# io_connectors.net
KiCad netlist of a schematic drawn in Altium Designer
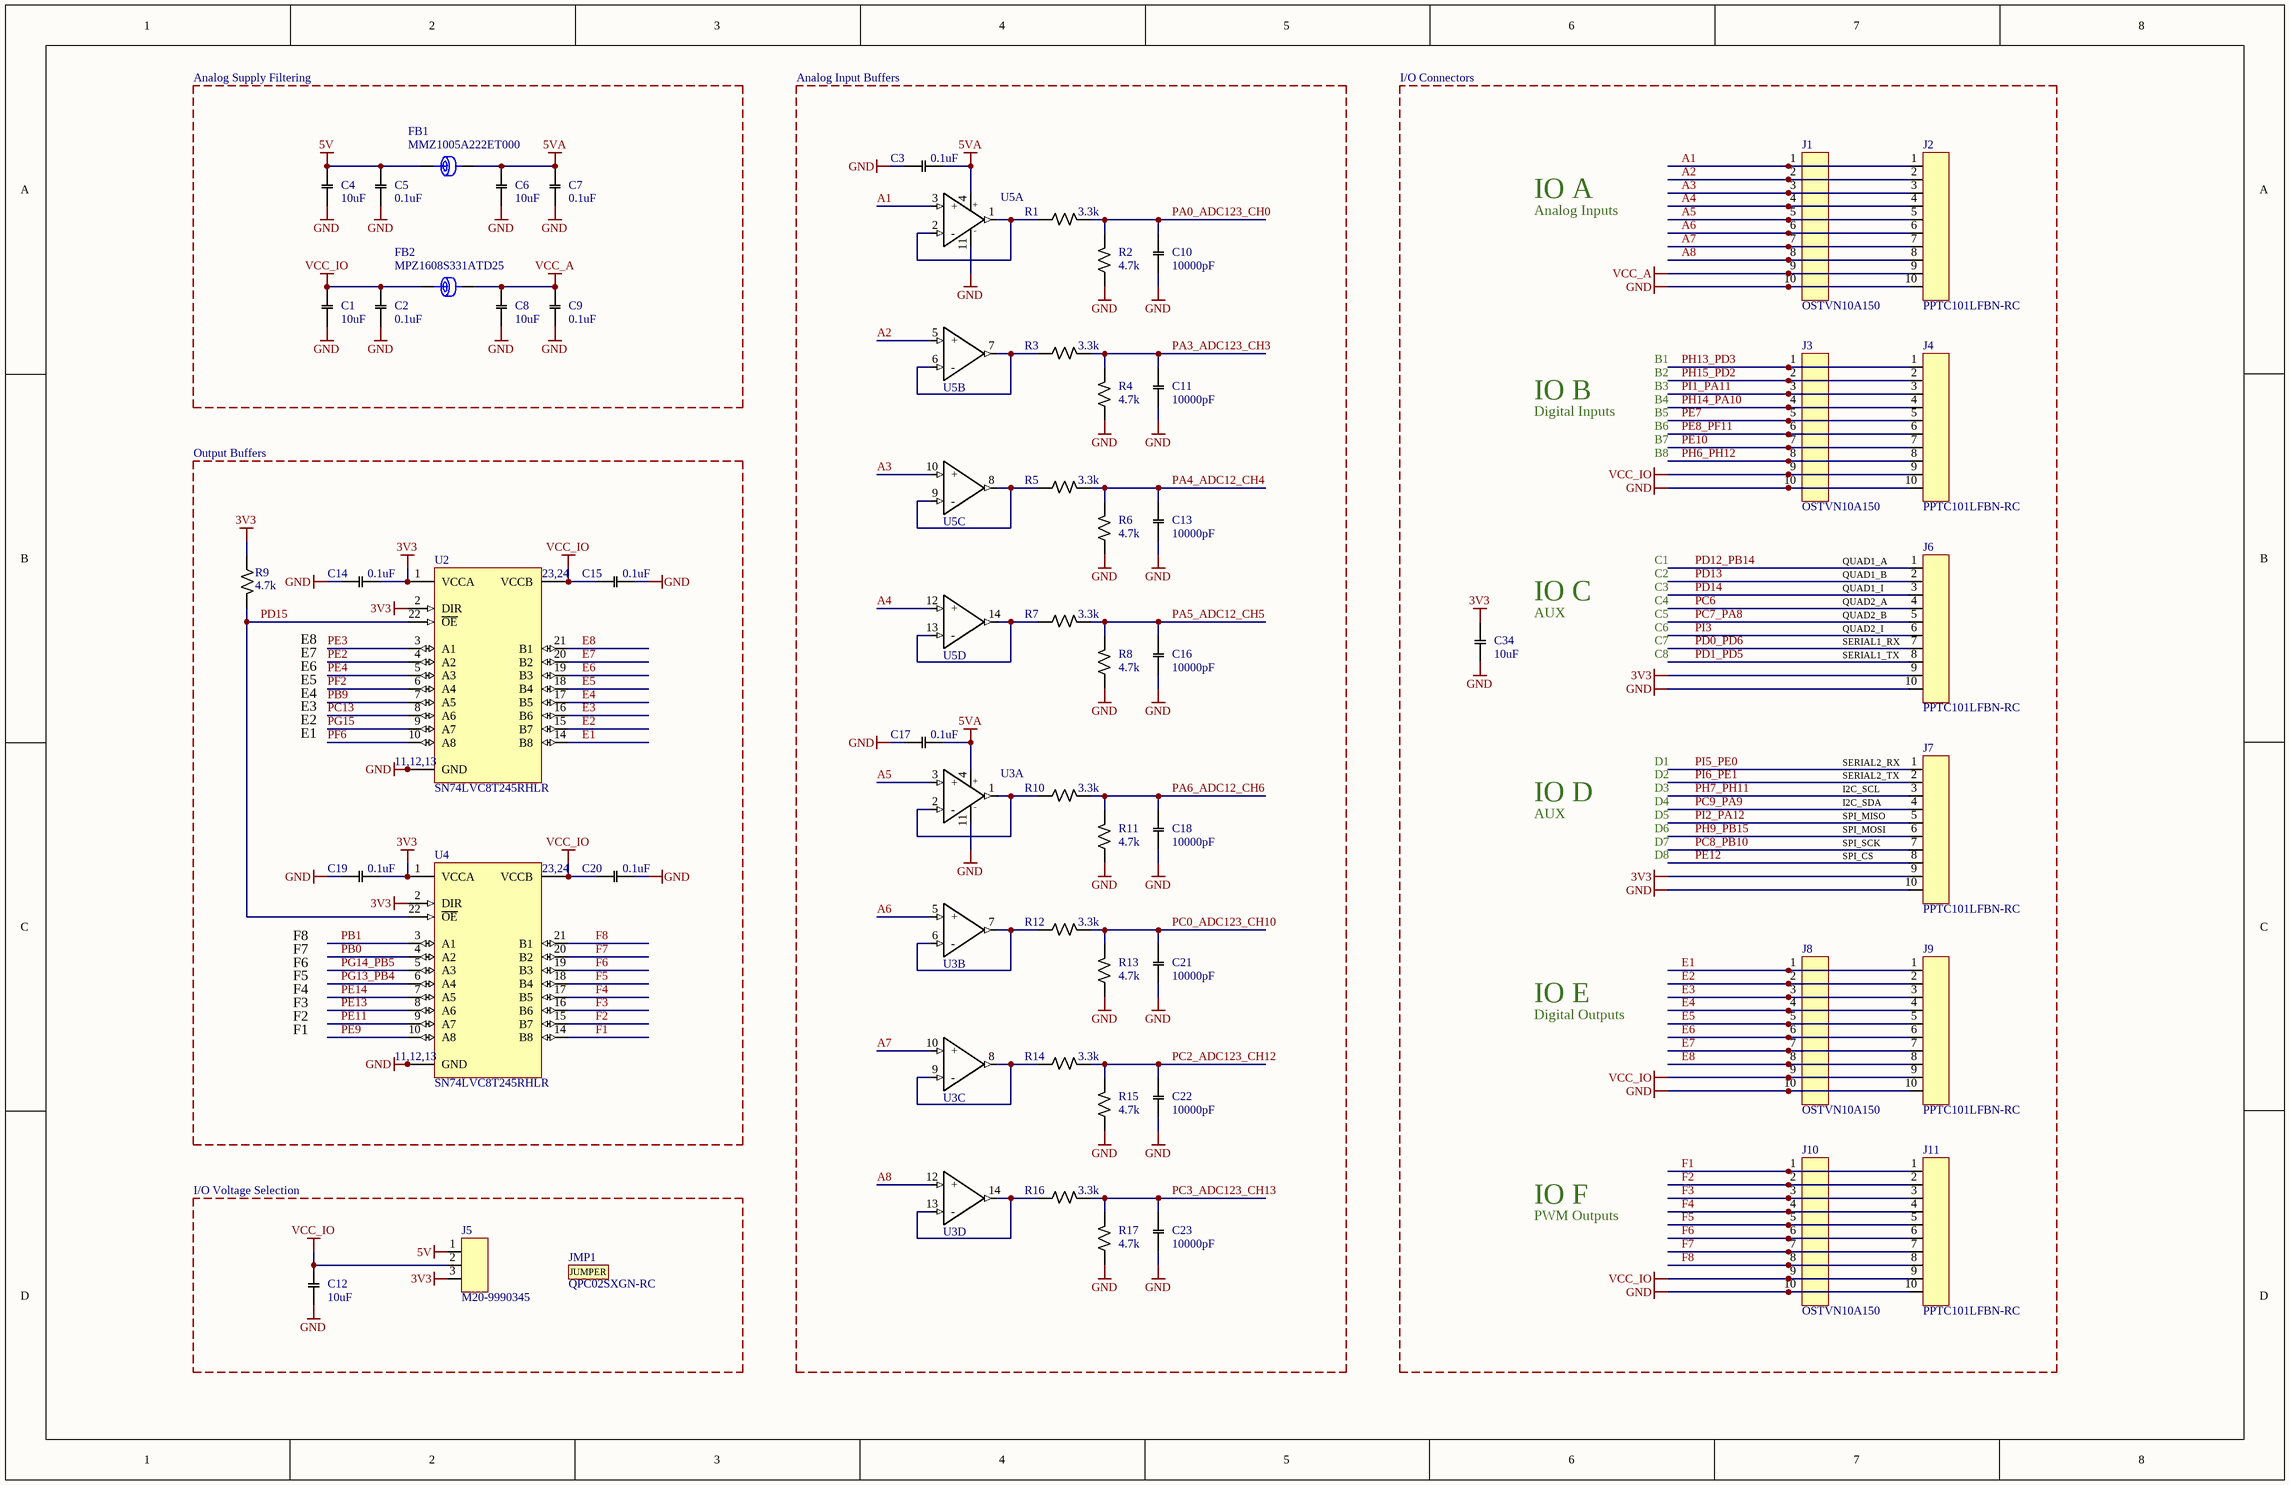
[diagram p0: io_connectors.SchDoc]

(export (version "E")
  (design (tool "Eeschema 10.0.6"))
  (components
    (comp (ref "C1")
      (value "C-10uf-X5R-25V-10%-0805")
      (footprint "C0805")
      (description "Capacitor Ceramic 10uF 25V X5R 10% SMD 0805")
      (fields (field (name "TOLERANCE") "10%") (field (name "CAPACITANCE") "10uF"))
      (libsource (lib "Hebi Robotics") (part "Capacitor"))
    )
    (comp (ref "C2")
      (value "C-0.1uf-X7R-25V-10%-0402")
      (footprint "C0402")
      (description "Capacitor Ceramic 0.1uF 25V X7R 10% SMD 0402")
      (fields (field (name "TOLERANCE") "10%") (field (name "CAPACITANCE") "0.1uF"))
      (libsource (lib "Hebi Robotics") (part "Capacitor"))
    )
    (comp (ref "C3")
      (value "C-0.1uf-X7R-25V-10%-0402")
      (footprint "C0402")
      (description "Capacitor Ceramic 0.1uF 25V X7R 10% SMD 0402")
      (fields (field (name "TOLERANCE") "10%") (field (name "CAPACITANCE") "0.1uF"))
      (libsource (lib "Hebi Robotics") (part "Capacitor"))
    )
    (comp (ref "C4")
      (value "C-10uf-X5R-25V-10%-0805")
      (footprint "C0805")
      (description "Capacitor Ceramic 10uF 25V X5R 10% SMD 0805")
      (fields (field (name "TOLERANCE") "10%") (field (name "CAPACITANCE") "10uF"))
      (libsource (lib "Hebi Robotics") (part "Capacitor"))
    )
    (comp (ref "C5")
      (value "C-0.1uf-X7R-25V-10%-0402")
      (footprint "C0402")
      (description "Capacitor Ceramic 0.1uF 25V X7R 10% SMD 0402")
      (fields (field (name "TOLERANCE") "10%") (field (name "CAPACITANCE") "0.1uF"))
      (libsource (lib "Hebi Robotics") (part "Capacitor"))
    )
    (comp (ref "C6")
      (value "C-10uf-X5R-25V-10%-0805")
      (footprint "C0805")
      (description "Capacitor Ceramic 10uF 25V X5R 10% SMD 0805")
      (fields (field (name "TOLERANCE") "10%") (field (name "CAPACITANCE") "10uF"))
      (libsource (lib "Hebi Robotics") (part "Capacitor"))
    )
    (comp (ref "C7")
      (value "C-0.1uf-X7R-25V-10%-0402")
      (footprint "C0402")
      (description "Capacitor Ceramic 0.1uF 25V X7R 10% SMD 0402")
      (fields (field (name "TOLERANCE") "10%") (field (name "CAPACITANCE") "0.1uF"))
      (libsource (lib "Hebi Robotics") (part "Capacitor"))
    )
    (comp (ref "C8")
      (value "C-10uf-X5R-25V-10%-0805")
      (footprint "C0805")
      (description "Capacitor Ceramic 10uF 25V X5R 10% SMD 0805")
      (fields (field (name "TOLERANCE") "10%") (field (name "CAPACITANCE") "10uF"))
      (libsource (lib "Hebi Robotics") (part "Capacitor"))
    )
    (comp (ref "C9")
      (value "C-0.1uf-X7R-25V-10%-0402")
      (footprint "C0402")
      (description "Capacitor Ceramic 0.1uF 25V X7R 10% SMD 0402")
      (fields (field (name "TOLERANCE") "10%") (field (name "CAPACITANCE") "0.1uF"))
      (libsource (lib "Hebi Robotics") (part "Capacitor"))
    )
    (comp (ref "C10")
      (value "C-10000pf-X7R-50V-10%-0402")
      (footprint "C0402")
      (description "Capacitor Ceramic 10000pF 50V X7R 10% SMD 0402")
      (fields (field (name "TOLERANCE") "10%") (field (name "CAPACITANCE") "10000pF"))
      (libsource (lib "Hebi Robotics") (part "Capacitor"))
    )
    (comp (ref "C11")
      (value "C-10000pf-X7R-50V-10%-0402")
      (footprint "C0402")
      (description "Capacitor Ceramic 10000pF 50V X7R 10% SMD 0402")
      (fields (field (name "TOLERANCE") "10%") (field (name "CAPACITANCE") "10000pF"))
      (libsource (lib "Hebi Robotics") (part "Capacitor"))
    )
    (comp (ref "C12")
      (value "C-10uf-X5R-25V-10%-0805")
      (footprint "C0805")
      (description "Capacitor Ceramic 10uF 25V X5R 10% SMD 0805")
      (fields (field (name "TOLERANCE") "10%") (field (name "CAPACITANCE") "10uF"))
      (libsource (lib "Hebi Robotics") (part "Capacitor"))
    )
    (comp (ref "C13")
      (value "C-10000pf-X7R-50V-10%-0402")
      (footprint "C0402")
      (description "Capacitor Ceramic 10000pF 50V X7R 10% SMD 0402")
      (fields (field (name "TOLERANCE") "10%") (field (name "CAPACITANCE") "10000pF"))
      (libsource (lib "Hebi Robotics") (part "Capacitor"))
    )
    (comp (ref "C14")
      (value "C-0.1uf-X7R-25V-10%-0402")
      (footprint "C0402")
      (description "Capacitor Ceramic 0.1uF 25V X7R 10% SMD 0402")
      (fields (field (name "TOLERANCE") "10%") (field (name "CAPACITANCE") "0.1uF"))
      (libsource (lib "Hebi Robotics") (part "Capacitor"))
    )
    (comp (ref "C15")
      (value "C-0.1uf-X7R-25V-10%-0402")
      (footprint "C0402")
      (description "Capacitor Ceramic 0.1uF 25V X7R 10% SMD 0402")
      (fields (field (name "TOLERANCE") "10%") (field (name "CAPACITANCE") "0.1uF"))
      (libsource (lib "Hebi Robotics") (part "Capacitor"))
    )
    (comp (ref "C16")
      (value "C-10000pf-X7R-50V-10%-0402")
      (footprint "C0402")
      (description "Capacitor Ceramic 10000pF 50V X7R 10% SMD 0402")
      (fields (field (name "TOLERANCE") "10%") (field (name "CAPACITANCE") "10000pF"))
      (libsource (lib "Hebi Robotics") (part "Capacitor"))
    )
    (comp (ref "C17")
      (value "C-0.1uf-X7R-25V-10%-0402")
      (footprint "C0402")
      (description "Capacitor Ceramic 0.1uF 25V X7R 10% SMD 0402")
      (fields (field (name "TOLERANCE") "10%") (field (name "CAPACITANCE") "0.1uF"))
      (libsource (lib "Hebi Robotics") (part "Capacitor"))
    )
    (comp (ref "C18")
      (value "C-10000pf-X7R-50V-10%-0402")
      (footprint "C0402")
      (description "Capacitor Ceramic 10000pF 50V X7R 10% SMD 0402")
      (fields (field (name "TOLERANCE") "10%") (field (name "CAPACITANCE") "10000pF"))
      (libsource (lib "Hebi Robotics") (part "Capacitor"))
    )
    (comp (ref "C19")
      (value "C-0.1uf-X7R-25V-10%-0402")
      (footprint "C0402")
      (description "Capacitor Ceramic 0.1uF 25V X7R 10% SMD 0402")
      (fields (field (name "TOLERANCE") "10%") (field (name "CAPACITANCE") "0.1uF"))
      (libsource (lib "Hebi Robotics") (part "Capacitor"))
    )
    (comp (ref "C20")
      (value "C-0.1uf-X7R-25V-10%-0402")
      (footprint "C0402")
      (description "Capacitor Ceramic 0.1uF 25V X7R 10% SMD 0402")
      (fields (field (name "TOLERANCE") "10%") (field (name "CAPACITANCE") "0.1uF"))
      (libsource (lib "Hebi Robotics") (part "Capacitor"))
    )
    (comp (ref "C21")
      (value "C-10000pf-X7R-50V-10%-0402")
      (footprint "C0402")
      (description "Capacitor Ceramic 10000pF 50V X7R 10% SMD 0402")
      (fields (field (name "TOLERANCE") "10%") (field (name "CAPACITANCE") "10000pF"))
      (libsource (lib "Hebi Robotics") (part "Capacitor"))
    )
    (comp (ref "C22")
      (value "C-10000pf-X7R-50V-10%-0402")
      (footprint "C0402")
      (description "Capacitor Ceramic 10000pF 50V X7R 10% SMD 0402")
      (fields (field (name "TOLERANCE") "10%") (field (name "CAPACITANCE") "10000pF"))
      (libsource (lib "Hebi Robotics") (part "Capacitor"))
    )
    (comp (ref "C23")
      (value "C-10000pf-X7R-50V-10%-0402")
      (footprint "C0402")
      (description "Capacitor Ceramic 10000pF 50V X7R 10% SMD 0402")
      (fields (field (name "TOLERANCE") "10%") (field (name "CAPACITANCE") "10000pF"))
      (libsource (lib "Hebi Robotics") (part "Capacitor"))
    )
    (comp (ref "C34")
      (value "C-10uf-X5R-25V-10%-0805")
      (footprint "C0805")
      (description "Capacitor Ceramic 10uF 25V X5R 10% SMD 0805")
      (fields (field (name "TOLERANCE") "10%") (field (name "CAPACITANCE") "10uF"))
      (libsource (lib "Hebi Robotics") (part "Capacitor"))
    )
    (comp (ref "FB1")
      (value "MMZ1005A222ET000")
      (footprint "FB0402")
      (description "FERRITE BEAD 2.2 KOHM 0402 1LN")
      (libsource (lib "Hebi Robotics") (part "FB"))
    )
    (comp (ref "FB2")
      (value "MPZ1608S331ATD25")
      (footprint "FB0603")
      (description "FERRITE CHIP 330 OHM 1.7A 0603")
      (libsource (lib "Hebi Robotics") (part "FB"))
    )
    (comp (ref "J1")
      (value "OSTVN10A150")
      (footprint "OSTVN10A150")
      (description "CONN TERM BLOCK 2.54MM 10POS PCB")
      (fields (field (name "MANUFACTURER") "On Shore Technology Inc.") (field (name "VOLTAGE") "125V"))
      (libsource (lib "Hebi Robotics") (part "CONN_1_ROW_010_POS"))
    )
    (comp (ref "J2")
      (value "PPTC101LFBN-RC")
      (footprint "PPTC101LFBN-RC")
      (description "CONN HEADER FEMALE 10POS.1\" TIN")
      (fields (field (name "MANUFACTURER") "Sullins Connector Solutions"))
      (libsource (lib "Hebi Robotics") (part "CONN_1_ROW_010_POS"))
    )
    (comp (ref "J3")
      (value "OSTVN10A150")
      (footprint "OSTVN10A150")
      (description "CONN TERM BLOCK 2.54MM 10POS PCB")
      (fields (field (name "MANUFACTURER") "On Shore Technology Inc.") (field (name "VOLTAGE") "125V"))
      (libsource (lib "Hebi Robotics") (part "CONN_1_ROW_010_POS"))
    )
    (comp (ref "J4")
      (value "PPTC101LFBN-RC")
      (footprint "PPTC101LFBN-RC")
      (description "CONN HEADER FEMALE 10POS.1\" TIN")
      (fields (field (name "MANUFACTURER") "Sullins Connector Solutions"))
      (libsource (lib "Hebi Robotics") (part "CONN_1_ROW_010_POS"))
    )
    (comp (ref "J5")
      (value "M20-9990345")
      (footprint "M20-9990345")
      (description "CONN HEADER VERT 3POS 2.54MM")
      (fields (field (name "MANUFACTURER") "Harwin Inc."))
      (libsource (lib "Hebi Robotics") (part "CONN_1_ROW_003_POS"))
    )
    (comp (ref "J6")
      (value "PPTC101LFBN-RC")
      (footprint "PPTC101LFBN-RC")
      (description "CONN HEADER FEMALE 10POS.1\" TIN")
      (fields (field (name "MANUFACTURER") "Sullins Connector Solutions"))
      (libsource (lib "Hebi Robotics") (part "CONN_1_ROW_010_POS"))
    )
    (comp (ref "J7")
      (value "PPTC101LFBN-RC")
      (footprint "PPTC101LFBN-RC")
      (description "CONN HEADER FEMALE 10POS.1\" TIN")
      (fields (field (name "MANUFACTURER") "Sullins Connector Solutions"))
      (libsource (lib "Hebi Robotics") (part "CONN_1_ROW_010_POS"))
    )
    (comp (ref "J8")
      (value "OSTVN10A150")
      (footprint "OSTVN10A150")
      (description "CONN TERM BLOCK 2.54MM 10POS PCB")
      (fields (field (name "MANUFACTURER") "On Shore Technology Inc.") (field (name "VOLTAGE") "125V"))
      (libsource (lib "Hebi Robotics") (part "CONN_1_ROW_010_POS"))
    )
    (comp (ref "J9")
      (value "PPTC101LFBN-RC")
      (footprint "PPTC101LFBN-RC")
      (description "CONN HEADER FEMALE 10POS.1\" TIN")
      (fields (field (name "MANUFACTURER") "Sullins Connector Solutions"))
      (libsource (lib "Hebi Robotics") (part "CONN_1_ROW_010_POS"))
    )
    (comp (ref "J10")
      (value "OSTVN10A150")
      (footprint "OSTVN10A150")
      (description "CONN TERM BLOCK 2.54MM 10POS PCB")
      (fields (field (name "MANUFACTURER") "On Shore Technology Inc.") (field (name "VOLTAGE") "125V"))
      (libsource (lib "Hebi Robotics") (part "CONN_1_ROW_010_POS"))
    )
    (comp (ref "J11")
      (value "PPTC101LFBN-RC")
      (footprint "PPTC101LFBN-RC")
      (description "CONN HEADER FEMALE 10POS.1\" TIN")
      (fields (field (name "MANUFACTURER") "Sullins Connector Solutions"))
      (libsource (lib "Hebi Robotics") (part "CONN_1_ROW_010_POS"))
    )
    (comp (ref "JMP1")
      (value "QPC02SXGN-RC")
      (description "CONN JUMPER SHORTING .100\" GOLD")
      (fields (field (name "MANUFACTURER") "Sullins"))
      (libsource (lib "Hebi Robotics") (part "JUMPER_2"))
    )
    (comp (ref "R1")
      (value "R-3.3k-0.1%-0.063w-0402")
      (footprint "R0402")
      (description "Resistor 0402 3.3k Ohm 0.1% 1-16 Watt")
      (fields (field (name "POWER") "0.063W, 1/16W") (field (name "RESISTANCE") "3.3k"))
      (libsource (lib "Hebi Robotics") (part "Resistor"))
    )
    (comp (ref "R2")
      (value "R-4.7k-0.1%-0.063w-0402")
      (footprint "R0402")
      (description "Resistor 0402 4.7k Ohm 0.1% 1-16 Watt")
      (fields (field (name "POWER") "0.063W, 1/16W") (field (name "RESISTANCE") "4.7k"))
      (libsource (lib "Hebi Robotics") (part "Resistor"))
    )
    (comp (ref "R3")
      (value "R-3.3k-0.1%-0.063w-0402")
      (footprint "R0402")
      (description "Resistor 0402 3.3k Ohm 0.1% 1-16 Watt")
      (fields (field (name "POWER") "0.063W, 1/16W") (field (name "RESISTANCE") "3.3k"))
      (libsource (lib "Hebi Robotics") (part "Resistor"))
    )
    (comp (ref "R4")
      (value "R-4.7k-0.1%-0.063w-0402")
      (footprint "R0402")
      (description "Resistor 0402 4.7k Ohm 0.1% 1-16 Watt")
      (fields (field (name "POWER") "0.063W, 1/16W") (field (name "RESISTANCE") "4.7k"))
      (libsource (lib "Hebi Robotics") (part "Resistor"))
    )
    (comp (ref "R5")
      (value "R-3.3k-0.1%-0.063w-0402")
      (footprint "R0402")
      (description "Resistor 0402 3.3k Ohm 0.1% 1-16 Watt")
      (fields (field (name "POWER") "0.063W, 1/16W") (field (name "RESISTANCE") "3.3k"))
      (libsource (lib "Hebi Robotics") (part "Resistor"))
    )
    (comp (ref "R6")
      (value "R-4.7k-0.1%-0.063w-0402")
      (footprint "R0402")
      (description "Resistor 0402 4.7k Ohm 0.1% 1-16 Watt")
      (fields (field (name "POWER") "0.063W, 1/16W") (field (name "RESISTANCE") "4.7k"))
      (libsource (lib "Hebi Robotics") (part "Resistor"))
    )
    (comp (ref "R7")
      (value "R-3.3k-0.1%-0.063w-0402")
      (footprint "R0402")
      (description "Resistor 0402 3.3k Ohm 0.1% 1-16 Watt")
      (fields (field (name "POWER") "0.063W, 1/16W") (field (name "RESISTANCE") "3.3k"))
      (libsource (lib "Hebi Robotics") (part "Resistor"))
    )
    (comp (ref "R8")
      (value "R-4.7k-0.1%-0.063w-0402")
      (footprint "R0402")
      (description "Resistor 0402 4.7k Ohm 0.1% 1-16 Watt")
      (fields (field (name "POWER") "0.063W, 1/16W") (field (name "RESISTANCE") "4.7k"))
      (libsource (lib "Hebi Robotics") (part "Resistor"))
    )
    (comp (ref "R9")
      (value "R-4.7k-1%-0.063w-0402")
      (footprint "R0402")
      (description "Resistor 0402 4.7k Ohm 1% 1-16 Watt")
      (fields (field (name "POWER") "0.063W, 1/16W") (field (name "RESISTANCE") "4.7k"))
      (libsource (lib "Hebi Robotics") (part "Resistor"))
    )
    (comp (ref "R10")
      (value "R-3.3k-0.1%-0.063w-0402")
      (footprint "R0402")
      (description "Resistor 0402 3.3k Ohm 0.1% 1-16 Watt")
      (fields (field (name "POWER") "0.063W, 1/16W") (field (name "RESISTANCE") "3.3k"))
      (libsource (lib "Hebi Robotics") (part "Resistor"))
    )
    (comp (ref "R11")
      (value "R-4.7k-0.1%-0.063w-0402")
      (footprint "R0402")
      (description "Resistor 0402 4.7k Ohm 0.1% 1-16 Watt")
      (fields (field (name "POWER") "0.063W, 1/16W") (field (name "RESISTANCE") "4.7k"))
      (libsource (lib "Hebi Robotics") (part "Resistor"))
    )
    (comp (ref "R12")
      (value "R-3.3k-0.1%-0.063w-0402")
      (footprint "R0402")
      (description "Resistor 0402 3.3k Ohm 0.1% 1-16 Watt")
      (fields (field (name "POWER") "0.063W, 1/16W") (field (name "RESISTANCE") "3.3k"))
      (libsource (lib "Hebi Robotics") (part "Resistor"))
    )
    (comp (ref "R13")
      (value "R-4.7k-0.1%-0.063w-0402")
      (footprint "R0402")
      (description "Resistor 0402 4.7k Ohm 0.1% 1-16 Watt")
      (fields (field (name "POWER") "0.063W, 1/16W") (field (name "RESISTANCE") "4.7k"))
      (libsource (lib "Hebi Robotics") (part "Resistor"))
    )
    (comp (ref "R14")
      (value "R-3.3k-0.1%-0.063w-0402")
      (footprint "R0402")
      (description "Resistor 0402 3.3k Ohm 0.1% 1-16 Watt")
      (fields (field (name "POWER") "0.063W, 1/16W") (field (name "RESISTANCE") "3.3k"))
      (libsource (lib "Hebi Robotics") (part "Resistor"))
    )
    (comp (ref "R15")
      (value "R-4.7k-0.1%-0.063w-0402")
      (footprint "R0402")
      (description "Resistor 0402 4.7k Ohm 0.1% 1-16 Watt")
      (fields (field (name "POWER") "0.063W, 1/16W") (field (name "RESISTANCE") "4.7k"))
      (libsource (lib "Hebi Robotics") (part "Resistor"))
    )
    (comp (ref "R16")
      (value "R-3.3k-0.1%-0.063w-0402")
      (footprint "R0402")
      (description "Resistor 0402 3.3k Ohm 0.1% 1-16 Watt")
      (fields (field (name "POWER") "0.063W, 1/16W") (field (name "RESISTANCE") "3.3k"))
      (libsource (lib "Hebi Robotics") (part "Resistor"))
    )
    (comp (ref "R17")
      (value "R-4.7k-0.1%-0.063w-0402")
      (footprint "R0402")
      (description "Resistor 0402 4.7k Ohm 0.1% 1-16 Watt")
      (fields (field (name "POWER") "0.063W, 1/16W") (field (name "RESISTANCE") "4.7k"))
      (libsource (lib "Hebi Robotics") (part "Resistor"))
    )
    (comp (ref "U2")
      (value "SN74LVC8T245RHLR")
      (footprint "R-PVQFN-N24_TI")
      (description "IC BUS TRANSCVR 8BIT 24QFN")
      (libsource (lib "Hebi Robotics") (part "SN74LVC8T245"))
    )
    (comp (ref "U3")
      (value "TSV324IPT")
      (footprint "TSSOP14_ST")
      (description "IC OPAMP GP 1.4MHZ RRO 14TSSOP")
      (fields (field (name "MANUFACTURER") "STMicroelectronics"))
      (libsource (lib "Hebi Robotics") (part "Symbol"))
    )
    (comp (ref "U4")
      (value "SN74LVC8T245RHLR")
      (footprint "R-PVQFN-N24_TI")
      (description "IC BUS TRANSCVR 8BIT 24QFN")
      (libsource (lib "Hebi Robotics") (part "SN74LVC8T245"))
    )
    (comp (ref "U5")
      (value "TSV324IPT")
      (footprint "TSSOP14_ST")
      (description "IC OPAMP GP 1.4MHZ RRO 14TSSOP")
      (fields (field (name "MANUFACTURER") "STMicroelectronics"))
      (libsource (lib "Hebi Robotics") (part "Symbol"))
    )
  )
  (nets
    (net (code "1") (name "/A1") (class "Default")
      (node (ref "J1") (pin "1") (pinfunction "1_1") (pintype "passive"))
      (node (ref "J2") (pin "1") (pinfunction "1_1") (pintype "passive"))
      (node (ref "U5") (pin "3") (pinfunction "+_3") (pintype "input"))
    )
    (net (code "2") (name "/A2") (class "Default")
      (node (ref "J1") (pin "2") (pinfunction "2_2") (pintype "passive"))
      (node (ref "J2") (pin "2") (pinfunction "2_2") (pintype "passive"))
      (node (ref "U5") (pin "5") (pinfunction "+_5") (pintype "input"))
    )
    (net (code "3") (name "/A3") (class "Default")
      (node (ref "J1") (pin "3") (pinfunction "3_3") (pintype "passive"))
      (node (ref "J2") (pin "3") (pinfunction "3_3") (pintype "passive"))
      (node (ref "U5") (pin "10") (pinfunction "+_10") (pintype "input"))
    )
    (net (code "4") (name "/A4") (class "Default")
      (node (ref "J1") (pin "4") (pinfunction "4_4") (pintype "passive"))
      (node (ref "J2") (pin "4") (pinfunction "4_4") (pintype "passive"))
      (node (ref "U5") (pin "12") (pinfunction "+_12") (pintype "input"))
    )
    (net (code "5") (name "/A5") (class "Default")
      (node (ref "J1") (pin "5") (pinfunction "5_5") (pintype "passive"))
      (node (ref "J2") (pin "5") (pinfunction "5_5") (pintype "passive"))
      (node (ref "U3") (pin "3") (pinfunction "+_3") (pintype "input"))
    )
    (net (code "6") (name "/A6") (class "Default")
      (node (ref "J1") (pin "6") (pinfunction "6_6") (pintype "passive"))
      (node (ref "J2") (pin "6") (pinfunction "6_6") (pintype "passive"))
      (node (ref "U3") (pin "5") (pinfunction "+_5") (pintype "input"))
    )
    (net (code "7") (name "/A7") (class "Default")
      (node (ref "J1") (pin "7") (pinfunction "7_7") (pintype "passive"))
      (node (ref "J2") (pin "7") (pinfunction "7_7") (pintype "passive"))
      (node (ref "U3") (pin "10") (pinfunction "+_10") (pintype "input"))
    )
    (net (code "8") (name "/A8") (class "Default")
      (node (ref "J1") (pin "8") (pinfunction "8_8") (pintype "passive"))
      (node (ref "J2") (pin "8") (pinfunction "8_8") (pintype "passive"))
      (node (ref "U3") (pin "12") (pinfunction "+_12") (pintype "input"))
    )
    (net (code "9") (name "/E1") (class "Default")
      (node (ref "J8") (pin "1") (pinfunction "1_1") (pintype "passive"))
      (node (ref "J9") (pin "1") (pinfunction "1_1") (pintype "passive"))
      (node (ref "U2") (pin "14") (pinfunction "B8_14") (pintype "bidirectional"))
    )
    (net (code "10") (name "/E2") (class "Default")
      (node (ref "J8") (pin "2") (pinfunction "2_2") (pintype "passive"))
      (node (ref "J9") (pin "2") (pinfunction "2_2") (pintype "passive"))
      (node (ref "U2") (pin "15") (pinfunction "B7_15") (pintype "bidirectional"))
    )
    (net (code "11") (name "/E3") (class "Default")
      (node (ref "J8") (pin "3") (pinfunction "3_3") (pintype "passive"))
      (node (ref "J9") (pin "3") (pinfunction "3_3") (pintype "passive"))
      (node (ref "U2") (pin "16") (pinfunction "B6_16") (pintype "bidirectional"))
    )
    (net (code "12") (name "/E4") (class "Default")
      (node (ref "J8") (pin "4") (pinfunction "4_4") (pintype "passive"))
      (node (ref "J9") (pin "4") (pinfunction "4_4") (pintype "passive"))
      (node (ref "U2") (pin "17") (pinfunction "B5_17") (pintype "bidirectional"))
    )
    (net (code "13") (name "/E5") (class "Default")
      (node (ref "J8") (pin "5") (pinfunction "5_5") (pintype "passive"))
      (node (ref "J9") (pin "5") (pinfunction "5_5") (pintype "passive"))
      (node (ref "U2") (pin "18") (pinfunction "B4_18") (pintype "bidirectional"))
    )
    (net (code "14") (name "/E6") (class "Default")
      (node (ref "J8") (pin "6") (pinfunction "6_6") (pintype "passive"))
      (node (ref "J9") (pin "6") (pinfunction "6_6") (pintype "passive"))
      (node (ref "U2") (pin "19") (pinfunction "B3_19") (pintype "bidirectional"))
    )
    (net (code "15") (name "/E7") (class "Default")
      (node (ref "J8") (pin "7") (pinfunction "7_7") (pintype "passive"))
      (node (ref "J9") (pin "7") (pinfunction "7_7") (pintype "passive"))
      (node (ref "U2") (pin "20") (pinfunction "B2_20") (pintype "bidirectional"))
    )
    (net (code "16") (name "/E8") (class "Default")
      (node (ref "J8") (pin "8") (pinfunction "8_8") (pintype "passive"))
      (node (ref "J9") (pin "8") (pinfunction "8_8") (pintype "passive"))
      (node (ref "U2") (pin "21") (pinfunction "B1_21") (pintype "bidirectional"))
    )
    (net (code "17") (name "/F1") (class "Default")
      (node (ref "J10") (pin "1") (pinfunction "1_1") (pintype "passive"))
      (node (ref "J11") (pin "1") (pinfunction "1_1") (pintype "passive"))
      (node (ref "U4") (pin "14") (pinfunction "B8_14") (pintype "bidirectional"))
    )
    (net (code "18") (name "/F2") (class "Default")
      (node (ref "J10") (pin "2") (pinfunction "2_2") (pintype "passive"))
      (node (ref "J11") (pin "2") (pinfunction "2_2") (pintype "passive"))
      (node (ref "U4") (pin "15") (pinfunction "B7_15") (pintype "bidirectional"))
    )
    (net (code "19") (name "/F3") (class "Default")
      (node (ref "J10") (pin "3") (pinfunction "3_3") (pintype "passive"))
      (node (ref "J11") (pin "3") (pinfunction "3_3") (pintype "passive"))
      (node (ref "U4") (pin "16") (pinfunction "B6_16") (pintype "bidirectional"))
    )
    (net (code "20") (name "/F4") (class "Default")
      (node (ref "J10") (pin "4") (pinfunction "4_4") (pintype "passive"))
      (node (ref "J11") (pin "4") (pinfunction "4_4") (pintype "passive"))
      (node (ref "U4") (pin "17") (pinfunction "B5_17") (pintype "bidirectional"))
    )
    (net (code "21") (name "/F5") (class "Default")
      (node (ref "J10") (pin "5") (pinfunction "5_5") (pintype "passive"))
      (node (ref "J11") (pin "5") (pinfunction "5_5") (pintype "passive"))
      (node (ref "U4") (pin "18") (pinfunction "B4_18") (pintype "bidirectional"))
    )
    (net (code "22") (name "/F6") (class "Default")
      (node (ref "J10") (pin "6") (pinfunction "6_6") (pintype "passive"))
      (node (ref "J11") (pin "6") (pinfunction "6_6") (pintype "passive"))
      (node (ref "U4") (pin "19") (pinfunction "B3_19") (pintype "bidirectional"))
    )
    (net (code "23") (name "/F7") (class "Default")
      (node (ref "J10") (pin "7") (pinfunction "7_7") (pintype "passive"))
      (node (ref "J11") (pin "7") (pinfunction "7_7") (pintype "passive"))
      (node (ref "U4") (pin "20") (pinfunction "B2_20") (pintype "bidirectional"))
    )
    (net (code "24") (name "/F8") (class "Default")
      (node (ref "J10") (pin "8") (pinfunction "8_8") (pintype "passive"))
      (node (ref "J11") (pin "8") (pinfunction "8_8") (pintype "passive"))
      (node (ref "U4") (pin "21") (pinfunction "B1_21") (pintype "bidirectional"))
    )
    (net (code "25") (name "/PA0_ADC123_CH0") (class "Default")
      (node (ref "C10") (pin "2") (pinfunction "2_2") (pintype "passive"))
      (node (ref "R1") (pin "2") (pinfunction "2_2") (pintype "passive"))
      (node (ref "R2") (pin "2") (pinfunction "2_2") (pintype "passive"))
    )
    (net (code "26") (name "/PA3_ADC123_CH3") (class "Default")
      (node (ref "C11") (pin "2") (pinfunction "2_2") (pintype "passive"))
      (node (ref "R3") (pin "2") (pinfunction "2_2") (pintype "passive"))
      (node (ref "R4") (pin "2") (pinfunction "2_2") (pintype "passive"))
    )
    (net (code "27") (name "/PA4_ADC12_CH4") (class "Default")
      (node (ref "C13") (pin "2") (pinfunction "2_2") (pintype "passive"))
      (node (ref "R5") (pin "2") (pinfunction "2_2") (pintype "passive"))
      (node (ref "R6") (pin "2") (pinfunction "2_2") (pintype "passive"))
    )
    (net (code "28") (name "/PA5_ADC12_CH5") (class "Default")
      (node (ref "C16") (pin "2") (pinfunction "2_2") (pintype "passive"))
      (node (ref "R7") (pin "2") (pinfunction "2_2") (pintype "passive"))
      (node (ref "R8") (pin "2") (pinfunction "2_2") (pintype "passive"))
    )
    (net (code "29") (name "/PA6_ADC12_CH6") (class "Default")
      (node (ref "C18") (pin "2") (pinfunction "2_2") (pintype "passive"))
      (node (ref "R10") (pin "2") (pinfunction "2_2") (pintype "passive"))
      (node (ref "R11") (pin "2") (pinfunction "2_2") (pintype "passive"))
    )
    (net (code "30") (name "/PB0") (class "Default")
      (node (ref "U4") (pin "4") (pinfunction "A2_4") (pintype "bidirectional"))
    )
    (net (code "31") (name "/PB1") (class "Default")
      (node (ref "U4") (pin "3") (pinfunction "A1_3") (pintype "bidirectional"))
    )
    (net (code "32") (name "/PB9") (class "Default")
      (node (ref "U2") (pin "7") (pinfunction "A5_7") (pintype "bidirectional"))
    )
    (net (code "33") (name "/PC0_ADC123_CH10") (class "Default")
      (node (ref "C21") (pin "2") (pinfunction "2_2") (pintype "passive"))
      (node (ref "R12") (pin "2") (pinfunction "2_2") (pintype "passive"))
      (node (ref "R13") (pin "2") (pinfunction "2_2") (pintype "passive"))
    )
    (net (code "34") (name "/PC2_ADC123_CH12") (class "Default")
      (node (ref "C22") (pin "2") (pinfunction "2_2") (pintype "passive"))
      (node (ref "R14") (pin "2") (pinfunction "2_2") (pintype "passive"))
      (node (ref "R15") (pin "2") (pinfunction "2_2") (pintype "passive"))
    )
    (net (code "35") (name "/PC3_ADC123_CH13") (class "Default")
      (node (ref "C23") (pin "2") (pinfunction "2_2") (pintype "passive"))
      (node (ref "R16") (pin "2") (pinfunction "2_2") (pintype "passive"))
      (node (ref "R17") (pin "2") (pinfunction "2_2") (pintype "passive"))
    )
    (net (code "36") (name "/PC6") (class "Default")
      (node (ref "J6") (pin "4") (pinfunction "4_4") (pintype "passive"))
    )
    (net (code "37") (name "/PC7_PA8") (class "Default")
      (node (ref "J6") (pin "5") (pinfunction "5_5") (pintype "passive"))
    )
    (net (code "38") (name "/PC8_PB10") (class "Default")
      (node (ref "J7") (pin "7") (pinfunction "7_7") (pintype "passive"))
    )
    (net (code "39") (name "/PC9_PA9") (class "Default")
      (node (ref "J7") (pin "4") (pinfunction "4_4") (pintype "passive"))
    )
    (net (code "40") (name "/PC13") (class "Default")
      (node (ref "U2") (pin "8") (pinfunction "A6_8") (pintype "bidirectional"))
    )
    (net (code "41") (name "/PD0_PD6") (class "Default")
      (node (ref "J6") (pin "7") (pinfunction "7_7") (pintype "passive"))
    )
    (net (code "42") (name "/PD1_PD5") (class "Default")
      (node (ref "J6") (pin "8") (pinfunction "8_8") (pintype "passive"))
    )
    (net (code "43") (name "/PD12_PB14") (class "Default")
      (node (ref "J6") (pin "1") (pinfunction "1_1") (pintype "passive"))
    )
    (net (code "44") (name "/PD13") (class "Default")
      (node (ref "J6") (pin "2") (pinfunction "2_2") (pintype "passive"))
    )
    (net (code "45") (name "/PD14") (class "Default")
      (node (ref "J6") (pin "3") (pinfunction "3_3") (pintype "passive"))
    )
    (net (code "46") (name "/PD15") (class "Default")
      (node (ref "R9") (pin "2") (pinfunction "2_2") (pintype "passive"))
      (node (ref "U2") (pin "22") (pinfunction "OE_22") (pintype "input"))
      (node (ref "U4") (pin "22") (pinfunction "OE_22") (pintype "input"))
    )
    (net (code "47") (name "/PE2") (class "Default")
      (node (ref "U2") (pin "4") (pinfunction "A2_4") (pintype "bidirectional"))
    )
    (net (code "48") (name "/PE3") (class "Default")
      (node (ref "U2") (pin "3") (pinfunction "A1_3") (pintype "bidirectional"))
    )
    (net (code "49") (name "/PE4") (class "Default")
      (node (ref "U2") (pin "5") (pinfunction "A3_5") (pintype "bidirectional"))
    )
    (net (code "50") (name "/PE7") (class "Default")
      (node (ref "J3") (pin "5") (pinfunction "5_5") (pintype "passive"))
      (node (ref "J4") (pin "5") (pinfunction "5_5") (pintype "passive"))
    )
    (net (code "51") (name "/PE8_PF11") (class "Default")
      (node (ref "J3") (pin "6") (pinfunction "6_6") (pintype "passive"))
      (node (ref "J4") (pin "6") (pinfunction "6_6") (pintype "passive"))
    )
    (net (code "52") (name "/PE9") (class "Default")
      (node (ref "U4") (pin "10") (pinfunction "A8_10") (pintype "bidirectional"))
    )
    (net (code "53") (name "/PE10") (class "Default")
      (node (ref "J3") (pin "7") (pinfunction "7_7") (pintype "passive"))
      (node (ref "J4") (pin "7") (pinfunction "7_7") (pintype "passive"))
    )
    (net (code "54") (name "/PE11") (class "Default")
      (node (ref "U4") (pin "9") (pinfunction "A7_9") (pintype "bidirectional"))
    )
    (net (code "55") (name "/PE12") (class "Default")
      (node (ref "J7") (pin "8") (pinfunction "8_8") (pintype "passive"))
    )
    (net (code "56") (name "/PE13") (class "Default")
      (node (ref "U4") (pin "8") (pinfunction "A6_8") (pintype "bidirectional"))
    )
    (net (code "57") (name "/PE14") (class "Default")
      (node (ref "U4") (pin "7") (pinfunction "A5_7") (pintype "bidirectional"))
    )
    (net (code "58") (name "/PF2") (class "Default")
      (node (ref "U2") (pin "6") (pinfunction "A4_6") (pintype "bidirectional"))
    )
    (net (code "59") (name "/PF6") (class "Default")
      (node (ref "U2") (pin "10") (pinfunction "A8_10") (pintype "bidirectional"))
    )
    (net (code "60") (name "/PG13_PB4") (class "Default")
      (node (ref "U4") (pin "6") (pinfunction "A4_6") (pintype "bidirectional"))
    )
    (net (code "61") (name "/PG14_PB5") (class "Default")
      (node (ref "U4") (pin "5") (pinfunction "A3_5") (pintype "bidirectional"))
    )
    (net (code "62") (name "/PG15") (class "Default")
      (node (ref "U2") (pin "9") (pinfunction "A7_9") (pintype "bidirectional"))
    )
    (net (code "63") (name "/PH6_PH12") (class "Default")
      (node (ref "J3") (pin "8") (pinfunction "8_8") (pintype "passive"))
      (node (ref "J4") (pin "8") (pinfunction "8_8") (pintype "passive"))
    )
    (net (code "64") (name "/PH7_PH11") (class "Default")
      (node (ref "J7") (pin "3") (pinfunction "3_3") (pintype "passive"))
    )
    (net (code "65") (name "/PH9_PB15") (class "Default")
      (node (ref "J7") (pin "6") (pinfunction "6_6") (pintype "passive"))
    )
    (net (code "66") (name "/PH13_PD3") (class "Default")
      (node (ref "J3") (pin "1") (pinfunction "1_1") (pintype "passive"))
      (node (ref "J4") (pin "1") (pinfunction "1_1") (pintype "passive"))
    )
    (net (code "67") (name "/PH14_PA10") (class "Default")
      (node (ref "J3") (pin "4") (pinfunction "4_4") (pintype "passive"))
      (node (ref "J4") (pin "4") (pinfunction "4_4") (pintype "passive"))
    )
    (net (code "68") (name "/PH15_PD2") (class "Default")
      (node (ref "J3") (pin "2") (pinfunction "2_2") (pintype "passive"))
      (node (ref "J4") (pin "2") (pinfunction "2_2") (pintype "passive"))
    )
    (net (code "69") (name "/PI1_PA11") (class "Default")
      (node (ref "J3") (pin "3") (pinfunction "3_3") (pintype "passive"))
      (node (ref "J4") (pin "3") (pinfunction "3_3") (pintype "passive"))
    )
    (net (code "70") (name "/PI2_PA12") (class "Default")
      (node (ref "J7") (pin "5") (pinfunction "5_5") (pintype "passive"))
    )
    (net (code "71") (name "/PI3") (class "Default")
      (node (ref "J6") (pin "6") (pinfunction "6_6") (pintype "passive"))
    )
    (net (code "72") (name "/PI5_PE0") (class "Default")
      (node (ref "J7") (pin "1") (pinfunction "1_1") (pintype "passive"))
    )
    (net (code "73") (name "/PI6_PE1") (class "Default")
      (node (ref "J7") (pin "2") (pinfunction "2_2") (pintype "passive"))
    )
    (net (code "74") (name "3V3") (class "Default")
      (node (ref "C14") (pin "2") (pinfunction "2_2") (pintype "passive"))
      (node (ref "C19") (pin "2") (pinfunction "2_2") (pintype "passive"))
      (node (ref "C34") (pin "2") (pinfunction "2_2") (pintype "passive"))
      (node (ref "J5") (pin "3") (pinfunction "3_3") (pintype "passive"))
      (node (ref "J6") (pin "9") (pinfunction "9_9") (pintype "passive"))
      (node (ref "J7") (pin "9") (pinfunction "9_9") (pintype "passive"))
      (node (ref "R9") (pin "1") (pinfunction "1_1") (pintype "passive"))
      (node (ref "U2") (pin "1") (pinfunction "VCCA_1") (pintype "power_in"))
      (node (ref "U2") (pin "2") (pinfunction "DIR_2") (pintype "input"))
      (node (ref "U4") (pin "1") (pinfunction "VCCA_1") (pintype "power_in"))
      (node (ref "U4") (pin "2") (pinfunction "DIR_2") (pintype "input"))
    )
    (net (code "75") (name "5V") (class "Default")
      (node (ref "C4") (pin "2") (pinfunction "2_2") (pintype "passive"))
      (node (ref "C5") (pin "1") (pinfunction "1_1") (pintype "passive"))
      (node (ref "FB1") (pin "1") (pinfunction "1_1") (pintype "passive"))
      (node (ref "J5") (pin "1") (pinfunction "1_1") (pintype "passive"))
    )
    (net (code "76") (name "5VA") (class "Default")
      (node (ref "C17") (pin "1") (pinfunction "1_1") (pintype "passive"))
      (node (ref "C3") (pin "1") (pinfunction "1_1") (pintype "passive"))
      (node (ref "C6") (pin "2") (pinfunction "2_2") (pintype "passive"))
      (node (ref "C7") (pin "1") (pinfunction "1_1") (pintype "passive"))
      (node (ref "FB1") (pin "2") (pinfunction "2_2") (pintype "passive"))
      (node (ref "U3") (pin "4") (pinfunction "V+_4") (pintype "power_in"))
      (node (ref "U5") (pin "4") (pinfunction "V+_4") (pintype "power_in"))
    )
    (net (code "77") (name "GND") (class "Default")
      (node (ref "C1") (pin "1") (pinfunction "1_1") (pintype "passive"))
      (node (ref "C10") (pin "1") (pinfunction "1_1") (pintype "passive"))
      (node (ref "C11") (pin "1") (pinfunction "1_1") (pintype "passive"))
      (node (ref "C12") (pin "1") (pinfunction "1_1") (pintype "passive"))
      (node (ref "C13") (pin "1") (pinfunction "1_1") (pintype "passive"))
      (node (ref "C14") (pin "1") (pinfunction "1_1") (pintype "passive"))
      (node (ref "C15") (pin "1") (pinfunction "1_1") (pintype "passive"))
      (node (ref "C16") (pin "1") (pinfunction "1_1") (pintype "passive"))
      (node (ref "C17") (pin "2") (pinfunction "2_2") (pintype "passive"))
      (node (ref "C18") (pin "1") (pinfunction "1_1") (pintype "passive"))
      (node (ref "C19") (pin "1") (pinfunction "1_1") (pintype "passive"))
      (node (ref "C2") (pin "2") (pinfunction "2_2") (pintype "passive"))
      (node (ref "C20") (pin "1") (pinfunction "1_1") (pintype "passive"))
      (node (ref "C21") (pin "1") (pinfunction "1_1") (pintype "passive"))
      (node (ref "C22") (pin "1") (pinfunction "1_1") (pintype "passive"))
      (node (ref "C23") (pin "1") (pinfunction "1_1") (pintype "passive"))
      (node (ref "C3") (pin "2") (pinfunction "2_2") (pintype "passive"))
      (node (ref "C34") (pin "1") (pinfunction "1_1") (pintype "passive"))
      (node (ref "C4") (pin "1") (pinfunction "1_1") (pintype "passive"))
      (node (ref "C5") (pin "2") (pinfunction "2_2") (pintype "passive"))
      (node (ref "C6") (pin "1") (pinfunction "1_1") (pintype "passive"))
      (node (ref "C7") (pin "2") (pinfunction "2_2") (pintype "passive"))
      (node (ref "C8") (pin "1") (pinfunction "1_1") (pintype "passive"))
      (node (ref "C9") (pin "1") (pinfunction "1_1") (pintype "passive"))
      (node (ref "J1") (pin "10") (pinfunction "10_10") (pintype "passive"))
      (node (ref "J10") (pin "10") (pinfunction "10_10") (pintype "passive"))
      (node (ref "J11") (pin "10") (pinfunction "10_10") (pintype "passive"))
      (node (ref "J2") (pin "10") (pinfunction "10_10") (pintype "passive"))
      (node (ref "J3") (pin "10") (pinfunction "10_10") (pintype "passive"))
      (node (ref "J4") (pin "10") (pinfunction "10_10") (pintype "passive"))
      (node (ref "J6") (pin "10") (pinfunction "10_10") (pintype "passive"))
      (node (ref "J7") (pin "10") (pinfunction "10_10") (pintype "passive"))
      (node (ref "J8") (pin "10") (pinfunction "10_10") (pintype "passive"))
      (node (ref "J9") (pin "10") (pinfunction "10_10") (pintype "passive"))
      (node (ref "R11") (pin "1") (pinfunction "1_1") (pintype "passive"))
      (node (ref "R13") (pin "1") (pinfunction "1_1") (pintype "passive"))
      (node (ref "R15") (pin "1") (pinfunction "1_1") (pintype "passive"))
      (node (ref "R17") (pin "1") (pinfunction "1_1") (pintype "passive"))
      (node (ref "R2") (pin "1") (pinfunction "1_1") (pintype "passive"))
      (node (ref "R4") (pin "1") (pinfunction "1_1") (pintype "passive"))
      (node (ref "R6") (pin "1") (pinfunction "1_1") (pintype "passive"))
      (node (ref "R8") (pin "1") (pinfunction "1_1") (pintype "passive"))
      (node (ref "U2") (pin "11") (pinfunction "GND_11") (pintype "power_in"))
      (node (ref "U2") (pin "12") (pinfunction "GND_12") (pintype "power_in"))
      (node (ref "U2") (pin "13") (pinfunction "GND_13") (pintype "power_in"))
      (node (ref "U3") (pin "11") (pinfunction "V-_11") (pintype "power_in"))
      (node (ref "U4") (pin "11") (pinfunction "GND_11") (pintype "power_in"))
      (node (ref "U4") (pin "12") (pinfunction "GND_12") (pintype "power_in"))
      (node (ref "U4") (pin "13") (pinfunction "GND_13") (pintype "power_in"))
      (node (ref "U5") (pin "11") (pinfunction "V-_11") (pintype "power_in"))
    )
    (net (code "78") (name "Net-(U3A--)") (class "Default")
      (node (ref "R10") (pin "1") (pinfunction "1_1") (pintype "passive"))
      (node (ref "U3") (pin "1") (pinfunction "OUT_1") (pintype "output"))
      (node (ref "U3") (pin "2") (pinfunction "-_2") (pintype "input"))
    )
    (net (code "79") (name "Net-(U3B--)") (class "Default")
      (node (ref "R12") (pin "1") (pinfunction "1_1") (pintype "passive"))
      (node (ref "U3") (pin "6") (pinfunction "-_6") (pintype "input"))
      (node (ref "U3") (pin "7") (pinfunction "OUT_7") (pintype "output"))
    )
    (net (code "80") (name "Net-(U3C--)") (class "Default")
      (node (ref "R14") (pin "1") (pinfunction "1_1") (pintype "passive"))
      (node (ref "U3") (pin "8") (pinfunction "OUT_8") (pintype "output"))
      (node (ref "U3") (pin "9") (pinfunction "-_9") (pintype "input"))
    )
    (net (code "81") (name "Net-(U3D--)") (class "Default")
      (node (ref "R16") (pin "1") (pinfunction "1_1") (pintype "passive"))
      (node (ref "U3") (pin "13") (pinfunction "-_13") (pintype "input"))
      (node (ref "U3") (pin "14") (pinfunction "OUT_14") (pintype "output"))
    )
    (net (code "82") (name "Net-(U5A--)") (class "Default")
      (node (ref "R1") (pin "1") (pinfunction "1_1") (pintype "passive"))
      (node (ref "U5") (pin "1") (pinfunction "OUT_1") (pintype "output"))
      (node (ref "U5") (pin "2") (pinfunction "-_2") (pintype "input"))
    )
    (net (code "83") (name "Net-(U5B--)") (class "Default")
      (node (ref "R3") (pin "1") (pinfunction "1_1") (pintype "passive"))
      (node (ref "U5") (pin "6") (pinfunction "-_6") (pintype "input"))
      (node (ref "U5") (pin "7") (pinfunction "OUT_7") (pintype "output"))
    )
    (net (code "84") (name "Net-(U5C--)") (class "Default")
      (node (ref "R5") (pin "1") (pinfunction "1_1") (pintype "passive"))
      (node (ref "U5") (pin "8") (pinfunction "OUT_8") (pintype "output"))
      (node (ref "U5") (pin "9") (pinfunction "-_9") (pintype "input"))
    )
    (net (code "85") (name "Net-(U5D--)") (class "Default")
      (node (ref "R7") (pin "1") (pinfunction "1_1") (pintype "passive"))
      (node (ref "U5") (pin "13") (pinfunction "-_13") (pintype "input"))
      (node (ref "U5") (pin "14") (pinfunction "OUT_14") (pintype "output"))
    )
    (net (code "86") (name "VCC_A") (class "Default")
      (node (ref "C8") (pin "2") (pinfunction "2_2") (pintype "passive"))
      (node (ref "C9") (pin "2") (pinfunction "2_2") (pintype "passive"))
      (node (ref "FB2") (pin "2") (pinfunction "2_2") (pintype "passive"))
      (node (ref "J1") (pin "9") (pinfunction "9_9") (pintype "passive"))
      (node (ref "J2") (pin "9") (pinfunction "9_9") (pintype "passive"))
    )
    (net (code "87") (name "VCC_IO") (class "Default")
      (node (ref "C1") (pin "2") (pinfunction "2_2") (pintype "passive"))
      (node (ref "C12") (pin "2") (pinfunction "2_2") (pintype "passive"))
      (node (ref "C15") (pin "2") (pinfunction "2_2") (pintype "passive"))
      (node (ref "C2") (pin "1") (pinfunction "1_1") (pintype "passive"))
      (node (ref "C20") (pin "2") (pinfunction "2_2") (pintype "passive"))
      (node (ref "FB2") (pin "1") (pinfunction "1_1") (pintype "passive"))
      (node (ref "J10") (pin "9") (pinfunction "9_9") (pintype "passive"))
      (node (ref "J11") (pin "9") (pinfunction "9_9") (pintype "passive"))
      (node (ref "J3") (pin "9") (pinfunction "9_9") (pintype "passive"))
      (node (ref "J4") (pin "9") (pinfunction "9_9") (pintype "passive"))
      (node (ref "J5") (pin "2") (pinfunction "2_2") (pintype "passive"))
      (node (ref "J8") (pin "9") (pinfunction "9_9") (pintype "passive"))
      (node (ref "J9") (pin "9") (pinfunction "9_9") (pintype "passive"))
      (node (ref "U2") (pin "23") (pinfunction "VCCB_23") (pintype "power_in"))
      (node (ref "U2") (pin "24") (pinfunction "VCCB_24") (pintype "power_in"))
      (node (ref "U4") (pin "23") (pinfunction "VCCB_23") (pintype "power_in"))
      (node (ref "U4") (pin "24") (pinfunction "VCCB_24") (pintype "power_in"))
    )
  )
)
